# FioSaber_Prototype_C.net
KiCad netlist of a schematic drawn in EAGLE
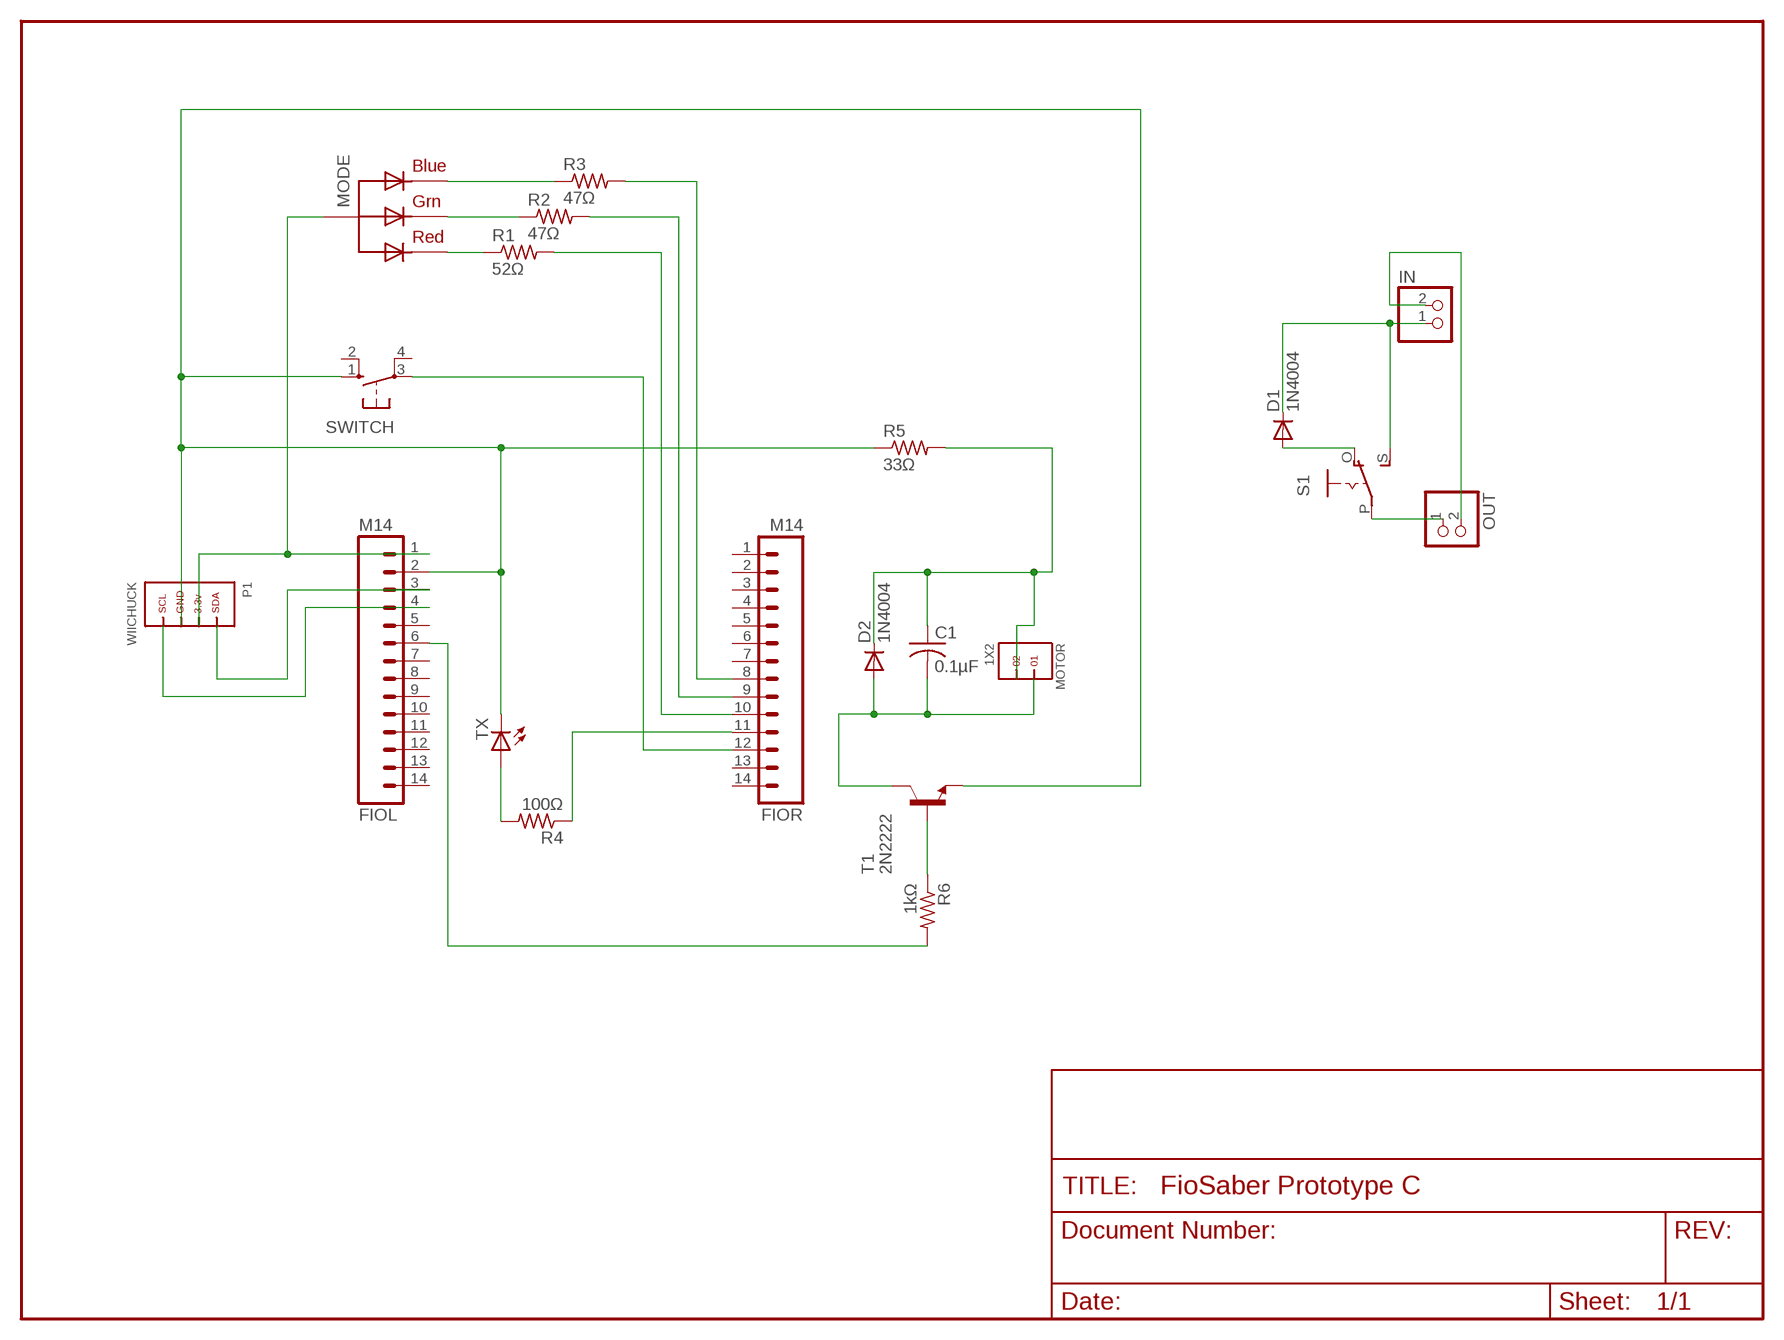
[diagram p0: schematic, sheet 1]

(export (version "E")
  (design (tool "Eeschema 10.0.6"))
  (components
    (comp (ref "C1")
      (value "0.1µF")
      (footprint "eagle-import:C025-025X050")
      (libsource (lib "eagle-import") (part "C-US025-025X050"))
    )
    (comp (ref "D1")
      (value "1N4004")
      (footprint "eagle-import:DO41-10")
      (libsource (lib "eagle-import") (part "1N4004"))
    )
    (comp (ref "D2")
      (value "1N4004")
      (footprint "eagle-import:DO41-10")
      (libsource (lib "eagle-import") (part "1N4004"))
    )
    (comp (ref "FIOL")
      (value "M14")
      (footprint "eagle-import:1X14")
      (libsource (lib "eagle-import") (part "M14"))
    )
    (comp (ref "FIOR")
      (value "M14")
      (footprint "eagle-import:1X14")
      (libsource (lib "eagle-import") (part "M14"))
    )
    (comp (ref "IN")
      (value "JST_2PIN-THM-RA")
      (footprint "eagle-import:JST-PH-2-THM-RA")
      (libsource (lib "eagle-import") (part "JST_2PIN-THM-RA"))
    )
    (comp (ref "MODE")
      (value "RGBLED_CA-PIRANHA")
      (footprint "eagle-import:PIRANHA5MM")
      (libsource (lib "eagle-import") (part "RGBLED_CA-PIRANHA"))
    )
    (comp (ref "MOTOR")
      (value "1X2")
      (footprint "eagle-import:1X2")
      (libsource (lib "eagle-import") (part "1X2"))
    )
    (comp (ref "OUT")
      (value "JST_2PIN-THM-RA")
      (footprint "eagle-import:JST-PH-2-THM-RA")
      (libsource (lib "eagle-import") (part "JST_2PIN-THM-RA"))
    )
    (comp (ref "P1")
      (value "WIICHUCK")
      (footprint "eagle-import:MEMOREX_RECEIVER")
      (libsource (lib "eagle-import") (part "WIICHUCK"))
    )
    (comp (ref "R1")
      (value "52Ω")
      (footprint "eagle-import:0207_7")
      (libsource (lib "eagle-import") (part "R-US_0207/7"))
    )
    (comp (ref "R2")
      (value "47Ω")
      (footprint "eagle-import:0207_7")
      (libsource (lib "eagle-import") (part "R-US_0207/7"))
    )
    (comp (ref "R3")
      (value "47Ω")
      (footprint "eagle-import:0207_7")
      (libsource (lib "eagle-import") (part "R-US_0207/7"))
    )
    (comp (ref "R4")
      (value "100Ω")
      (footprint "eagle-import:0207_7")
      (libsource (lib "eagle-import") (part "R-US_0207/7"))
    )
    (comp (ref "R5")
      (value "33Ω")
      (footprint "eagle-import:0207_7")
      (libsource (lib "eagle-import") (part "R-US_0207/7"))
    )
    (comp (ref "R6")
      (value "1kΩ")
      (footprint "eagle-import:0207_7")
      (libsource (lib "eagle-import") (part "R-US_0207/7"))
    )
    (comp (ref "S1")
      (value "EG1218S")
      (footprint "eagle-import:EG1218")
      (libsource (lib "eagle-import") (part "EG1218S"))
    )
    (comp (ref "SWITCH")
      (value "10-XX")
      (footprint "eagle-import:B3F-10XX")
      (fields (field (name "MPN") "B3F-1000"))
      (libsource (lib "eagle-import") (part "10-XX"))
    )
    (comp (ref "T1")
      (value "2N2222")
      (footprint "eagle-import:TO92-EBC-OVAL")
      (libsource (lib "eagle-import") (part "2N2222"))
    )
    (comp (ref "TX")
      (value "LED3MM")
      (footprint "eagle-import:LED3MM")
      (libsource (lib "eagle-import") (part "LED3MM"))
    )
  )
  (nets
    (net (code "1") (name "Net-(C1-Pad1)") (class "Default")
      (node (ref "C1") (pin "1") (pinfunction "1_1") (pintype "passive"))
      (node (ref "D2") (pin "C") (pinfunction "C_C") (pintype "passive"))
      (node (ref "MOTOR") (pin "2") (pinfunction "2_2") (pintype "bidirectional"))
      (node (ref "R5") (pin "2") (pinfunction "2_2") (pintype "passive"))
    )
    (net (code "2") (name "Net-(C1-Pad2)") (class "Default")
      (node (ref "C1") (pin "2") (pinfunction "2_2") (pintype "passive"))
      (node (ref "D2") (pin "A") (pinfunction "A_A") (pintype "passive"))
      (node (ref "MOTOR") (pin "1") (pinfunction "1_1") (pintype "bidirectional"))
      (node (ref "T1") (pin "C") (pinfunction "C_C") (pintype "passive"))
    )
    (net (code "3") (name "Net-(D1-PadA)") (class "Default")
      (node (ref "D1") (pin "A") (pinfunction "A_A") (pintype "passive"))
      (node (ref "S1") (pin "O") (pinfunction "O_O") (pintype "passive"))
    )
    (net (code "4") (name "Net-(FIOL-Pad3)") (class "Default")
      (node (ref "FIOL") (pin "3") (pinfunction "3_3") (pintype "passive"))
      (node (ref "P1") (pin "PWR") (pinfunction "PWR_PWR") (pintype "bidirectional"))
    )
    (net (code "5") (name "Net-(FIOL-Pad4)") (class "Default")
      (node (ref "FIOL") (pin "4") (pinfunction "4_4") (pintype "passive"))
      (node (ref "P1") (pin "GND") (pinfunction "GND_GND") (pintype "bidirectional"))
    )
    (net (code "6") (name "Net-(FIOL-Pad6)") (class "Default")
      (node (ref "FIOL") (pin "6") (pinfunction "6_6") (pintype "passive"))
      (node (ref "R6") (pin "2") (pinfunction "2_2") (pintype "passive"))
    )
    (net (code "7") (name "Net-(FIOR-Pad8)") (class "Default")
      (node (ref "FIOR") (pin "8") (pinfunction "8_8") (pintype "passive"))
      (node (ref "R3") (pin "2") (pinfunction "2_2") (pintype "passive"))
    )
    (net (code "8") (name "Net-(FIOR-Pad9)") (class "Default")
      (node (ref "FIOR") (pin "9") (pinfunction "9_9") (pintype "passive"))
      (node (ref "R2") (pin "2") (pinfunction "2_2") (pintype "passive"))
    )
    (net (code "9") (name "Net-(FIOR-Pad10)") (class "Default")
      (node (ref "FIOR") (pin "10") (pinfunction "10_10") (pintype "passive"))
      (node (ref "R1") (pin "2") (pinfunction "2_2") (pintype "passive"))
    )
    (net (code "10") (name "Net-(FIOR-Pad11)") (class "Default")
      (node (ref "FIOR") (pin "11") (pinfunction "11_11") (pintype "passive"))
      (node (ref "R4") (pin "1") (pinfunction "1_1") (pintype "passive"))
    )
    (net (code "11") (name "Net-(IN-1)") (class "Default")
      (node (ref "IN") (pin "2") (pinfunction "1_2") (pintype "passive"))
      (node (ref "OUT") (pin "2") (pinfunction "1_2") (pintype "passive"))
    )
    (net (code "12") (name "Net-(IN-2)") (class "Default")
      (node (ref "D1") (pin "C") (pinfunction "C_C") (pintype "passive"))
      (node (ref "IN") (pin "1") (pinfunction "2_1") (pintype "passive"))
      (node (ref "S1") (pin "S") (pinfunction "S_S") (pintype "passive"))
    )
    (net (code "13") (name "Net-(MODE-BLUE)") (class "Default")
      (node (ref "MODE") (pin "1") (pinfunction "BLUE_1") (pintype "bidirectional"))
      (node (ref "R3") (pin "1") (pinfunction "1_1") (pintype "passive"))
    )
    (net (code "14") (name "Net-(MODE-GREEN)") (class "Default")
      (node (ref "MODE") (pin "3") (pinfunction "GREEN_3") (pintype "bidirectional"))
      (node (ref "R2") (pin "1") (pinfunction "1_1") (pintype "passive"))
    )
    (net (code "15") (name "Net-(MODE-RED)") (class "Default")
      (node (ref "MODE") (pin "2") (pinfunction "RED_2") (pintype "bidirectional"))
      (node (ref "R1") (pin "1") (pinfunction "1_1") (pintype "passive"))
    )
    (net (code "16") (name "Net-(MODE-VCC)") (class "Default")
      (node (ref "FIOL") (pin "1") (pinfunction "1_1") (pintype "passive"))
      (node (ref "MODE") (pin "4") (pinfunction "VCC_4") (pintype "bidirectional"))
      (node (ref "P1") (pin "SDA") (pinfunction "SDA_SDA") (pintype "bidirectional"))
    )
    (net (code "17") (name "Net-(OUT-2)") (class "Default")
      (node (ref "OUT") (pin "1") (pinfunction "2_1") (pintype "passive"))
      (node (ref "S1") (pin "P") (pinfunction "P_P") (pintype "passive"))
    )
    (net (code "18") (name "Net-(R4-Pad2)") (class "Default")
      (node (ref "R4") (pin "2") (pinfunction "2_2") (pintype "passive"))
      (node (ref "TX") (pin "A") (pinfunction "A_A") (pintype "passive"))
    )
    (net (code "19") (name "Net-(R6-Pad1)") (class "Default")
      (node (ref "R6") (pin "1") (pinfunction "1_1") (pintype "passive"))
      (node (ref "T1") (pin "B") (pinfunction "B_B") (pintype "passive"))
    )
    (net (code "20") (name "Net-(SWITCH-P)") (class "Default")
      (node (ref "FIOR") (pin "12") (pinfunction "12_12") (pintype "passive"))
      (node (ref "SWITCH") (pin "3") (pinfunction "P_3") (pintype "passive"))
    )
    (net (code "21") (name "Net-(SWITCH-S)") (class "Default")
      (node (ref "FIOL") (pin "2") (pinfunction "2_2") (pintype "passive"))
      (node (ref "P1") (pin "SCL") (pinfunction "SCL_SCL") (pintype "bidirectional"))
      (node (ref "R5") (pin "1") (pinfunction "1_1") (pintype "passive"))
      (node (ref "SWITCH") (pin "1") (pinfunction "S_1") (pintype "passive"))
      (node (ref "T1") (pin "E") (pinfunction "E_E") (pintype "passive"))
      (node (ref "TX") (pin "K") (pinfunction "C_K") (pintype "passive"))
    )
    (net (code "22") (name "unconnected-(FIOL-Pad5)") (class "Default")
      (node (ref "FIOL") (pin "5") (pinfunction "5_5") (pintype "passive"))
    )
    (net (code "23") (name "unconnected-(FIOL-Pad7)") (class "Default")
      (node (ref "FIOL") (pin "7") (pinfunction "7_7") (pintype "passive"))
    )
    (net (code "24") (name "unconnected-(FIOL-Pad8)") (class "Default")
      (node (ref "FIOL") (pin "8") (pinfunction "8_8") (pintype "passive"))
    )
    (net (code "25") (name "unconnected-(FIOL-Pad9)") (class "Default")
      (node (ref "FIOL") (pin "9") (pinfunction "9_9") (pintype "passive"))
    )
    (net (code "26") (name "unconnected-(FIOL-Pad10)") (class "Default")
      (node (ref "FIOL") (pin "10") (pinfunction "10_10") (pintype "passive"))
    )
    (net (code "27") (name "unconnected-(FIOL-Pad11)") (class "Default")
      (node (ref "FIOL") (pin "11") (pinfunction "11_11") (pintype "passive"))
    )
    (net (code "28") (name "unconnected-(FIOL-Pad12)") (class "Default")
      (node (ref "FIOL") (pin "12") (pinfunction "12_12") (pintype "passive"))
    )
    (net (code "29") (name "unconnected-(FIOL-Pad13)") (class "Default")
      (node (ref "FIOL") (pin "13") (pinfunction "13_13") (pintype "passive"))
    )
    (net (code "30") (name "unconnected-(FIOL-Pad14)") (class "Default")
      (node (ref "FIOL") (pin "14") (pinfunction "14_14") (pintype "passive"))
    )
    (net (code "31") (name "unconnected-(FIOR-Pad1)") (class "Default")
      (node (ref "FIOR") (pin "1") (pinfunction "1_1") (pintype "passive"))
    )
    (net (code "32") (name "unconnected-(FIOR-Pad2)") (class "Default")
      (node (ref "FIOR") (pin "2") (pinfunction "2_2") (pintype "passive"))
    )
    (net (code "33") (name "unconnected-(FIOR-Pad3)") (class "Default")
      (node (ref "FIOR") (pin "3") (pinfunction "3_3") (pintype "passive"))
    )
    (net (code "34") (name "unconnected-(FIOR-Pad4)") (class "Default")
      (node (ref "FIOR") (pin "4") (pinfunction "4_4") (pintype "passive"))
    )
    (net (code "35") (name "unconnected-(FIOR-Pad5)") (class "Default")
      (node (ref "FIOR") (pin "5") (pinfunction "5_5") (pintype "passive"))
    )
    (net (code "36") (name "unconnected-(FIOR-Pad6)") (class "Default")
      (node (ref "FIOR") (pin "6") (pinfunction "6_6") (pintype "passive"))
    )
    (net (code "37") (name "unconnected-(FIOR-Pad7)") (class "Default")
      (node (ref "FIOR") (pin "7") (pinfunction "7_7") (pintype "passive"))
    )
    (net (code "38") (name "unconnected-(FIOR-Pad13)") (class "Default")
      (node (ref "FIOR") (pin "13") (pinfunction "13_13") (pintype "passive"))
    )
    (net (code "39") (name "unconnected-(FIOR-Pad14)") (class "Default")
      (node (ref "FIOR") (pin "14") (pinfunction "14_14") (pintype "passive"))
    )
    (net (code "40") (name "unconnected-(SWITCH-P1-Pad4)") (class "Default")
      (node (ref "SWITCH") (pin "4") (pinfunction "P1_4") (pintype "passive"))
    )
    (net (code "41") (name "unconnected-(SWITCH-S1-Pad2)") (class "Default")
      (node (ref "SWITCH") (pin "2") (pinfunction "S1_2") (pintype "passive"))
    )
  )
)
